# Sheet1.net
KiCad netlist of a schematic drawn in Altium Designer
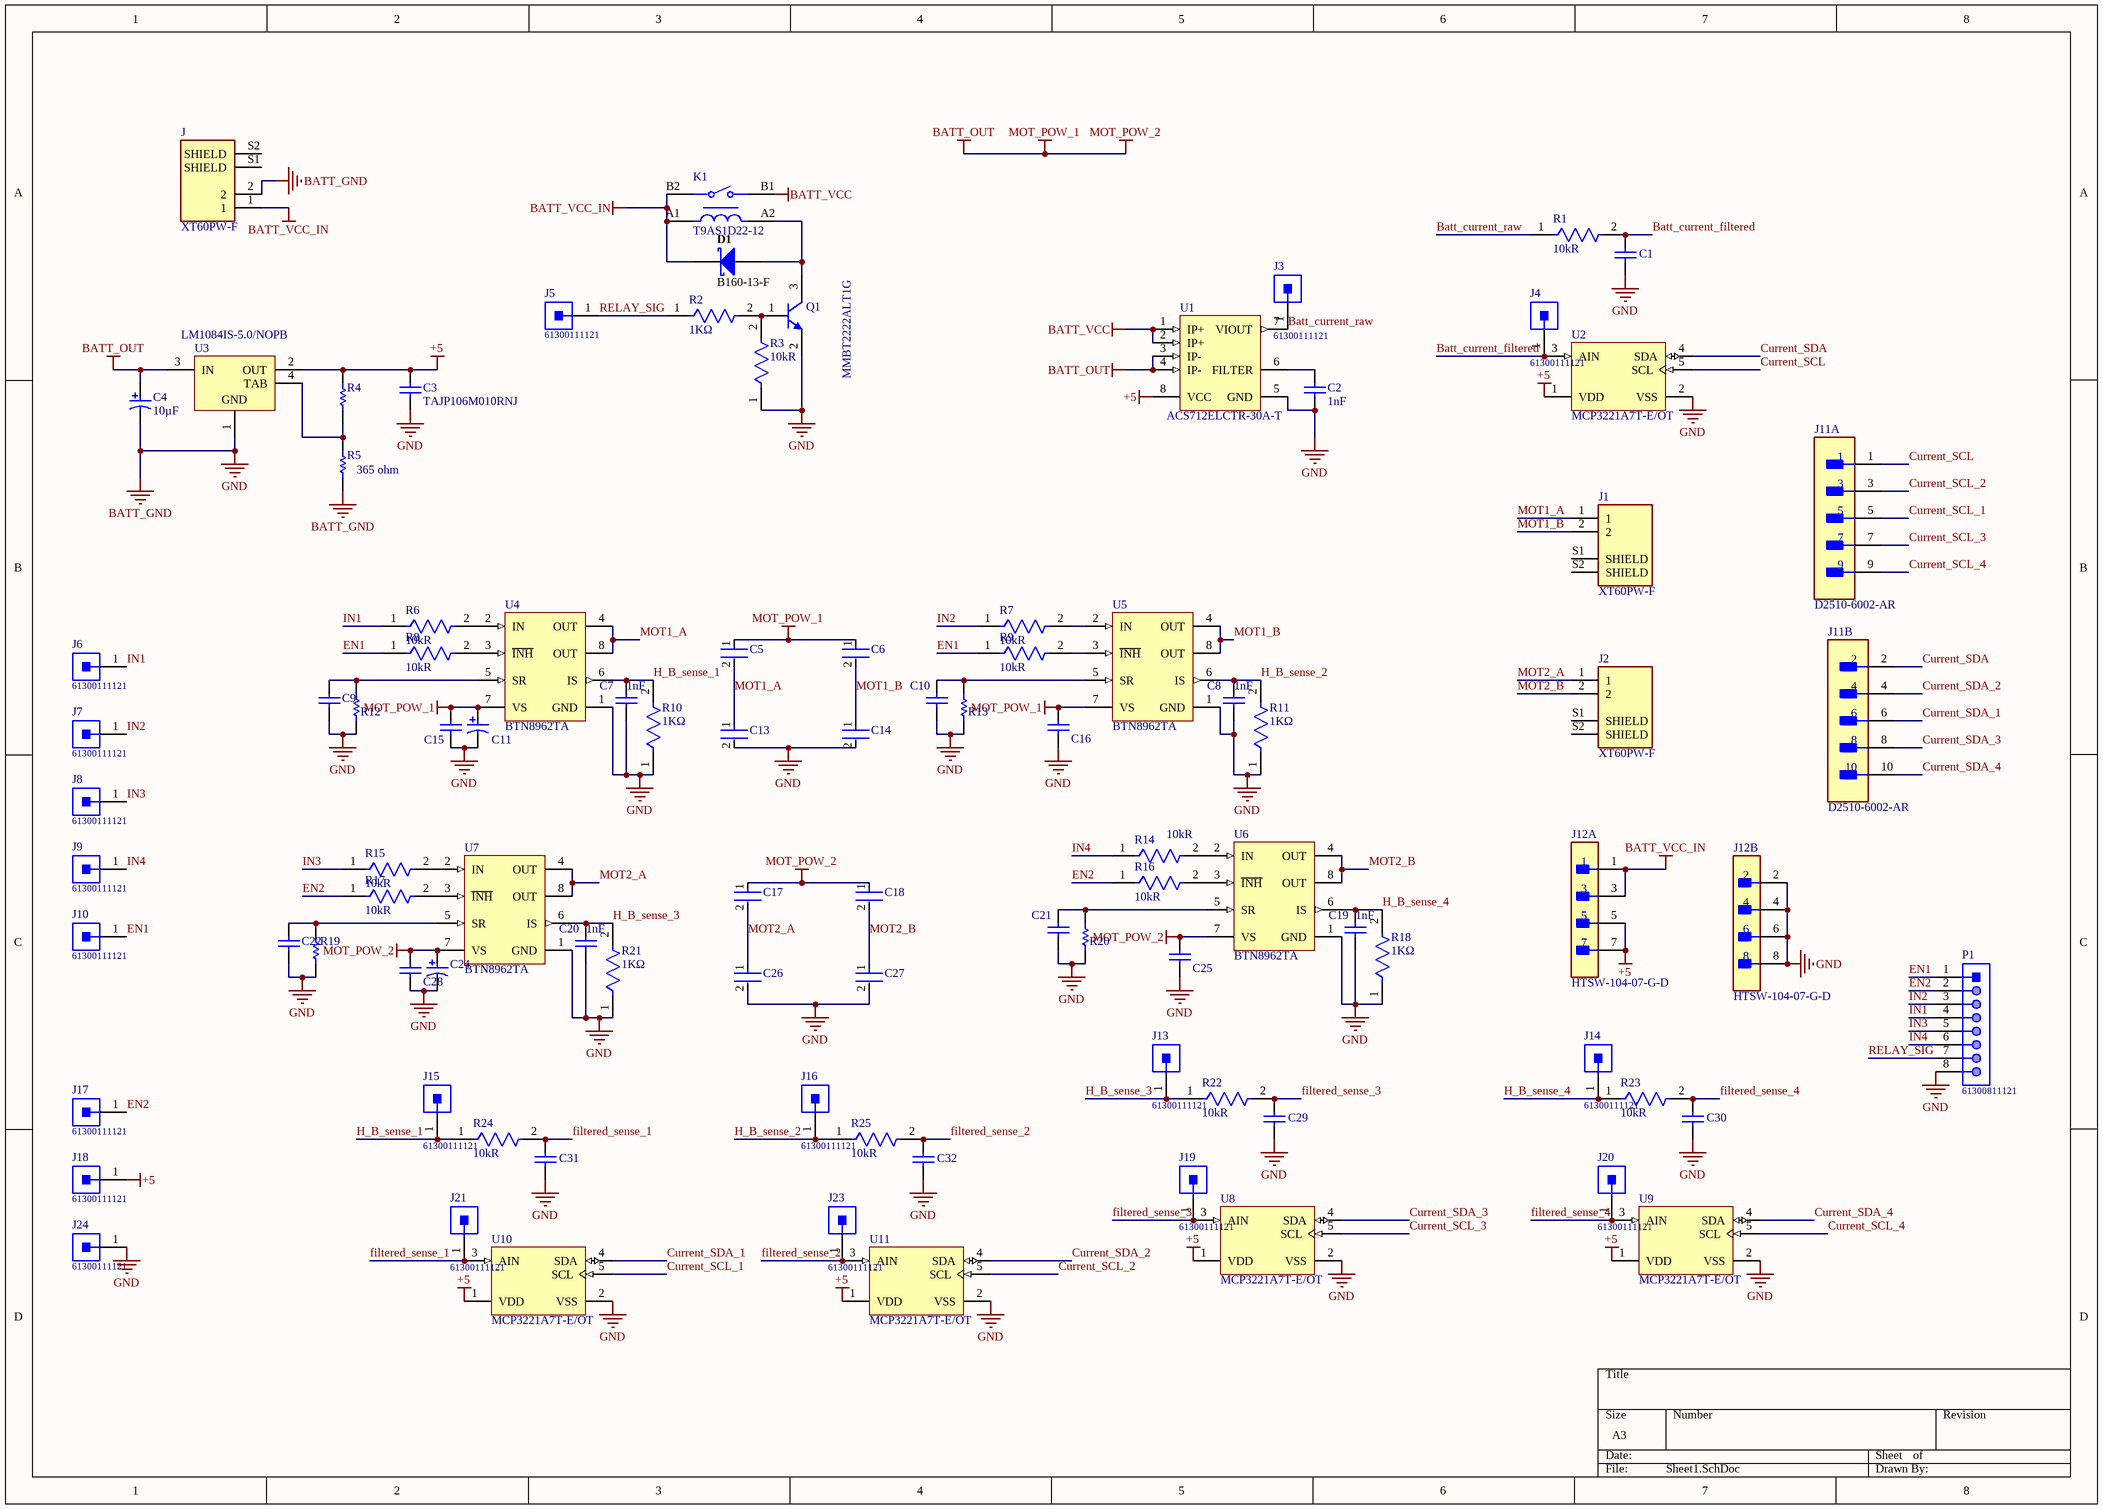
[diagram p0: Sheet1.SchDoc]

(export (version "E")
  (design (tool "Eeschema 10.0.6"))
  (components
    (comp (ref "C1")
      (value "GRM188R60J106ME47D")
      (footprint "CAPC1608X90X35NL10T15")
      (fields (field (name "MANUFACTURER") "Murata"))
      (libsource (lib "Altium Content Vault") (part "CAP"))
    )
    (comp (ref "C2")
      (value "1nF")
      (footprint "CAPC1608X95X40LL15T15")
      (fields (field (name "PART NUMBER") "VJ0603Y102KXACW1BC") (field (name "MANUFACTURER") "Vitramon"))
      (libsource (lib "Altium Content Vault") (part "CAP"))
    )
    (comp (ref "C3")
      (value "TAJP106M010RNJ")
      (footprint "CAPC2113X120X50ML20T30")
      (fields (field (name "MANUFACTURER") "AVX Interconnect / Elco"))
      (libsource (lib "Altium Content Vault") (part "CAP"))
    )
    (comp (ref "C4")
      (value "EEE-FK1V100UR")
      (footprint "PNSC-FK-V-B_V")
      (fields (field (name "MANUFACTURER") "Panasonic") (field (name "CAPACITANCE") "10µF"))
      (libsource (lib "Altium Content Vault") (part "CAP-P-2"))
    )
    (comp (ref "C5")
      (value "CC0805KRX7R7BB224")
      (footprint "FP-CC0805-0_85-MFG")
      (description "CAP CER 0.22UF 16V X7R 0805")
      (fields (field (name "TOLERANCE") "0.1") (field (name "MANUFACTURER") "Yageo"))
      (libsource (lib "Altium Content Vault") (part "11868f565c42a9108669ba33697ecf6"))
    )
    (comp (ref "C6")
      (value "CC0805KRX7R7BB224")
      (footprint "FP-CC0805-0_85-MFG")
      (description "CAP CER 0.22UF 16V X7R 0805")
      (fields (field (name "TOLERANCE") "0.1") (field (name "MANUFACTURER") "Yageo"))
      (libsource (lib "Altium Content Vault") (part "11868f565c42a9108669ba33697ecf6"))
    )
    (comp (ref "C7")
      (value "1nF")
      (footprint "CAPC1608X95X40LL15T15")
      (fields (field (name "PART NUMBER") "VJ0603Y102KXACW1BC") (field (name "MANUFACTURER") "Vitramon"))
      (libsource (lib "Altium Content Vault") (part "CAP"))
    )
    (comp (ref "C8")
      (value "1nF")
      (footprint "CAPC1608X95X40LL15T15")
      (fields (field (name "PART NUMBER") "VJ0603Y102KXACW1BC") (field (name "MANUFACTURER") "Vitramon"))
      (libsource (lib "Altium Content Vault") (part "CAP"))
    )
    (comp (ref "C9")
      (value "0603YC104KAZ2A")
      (footprint "CAPC1608X90X35ML15T15")
      (fields (field (name "MANUFACTURER") "AVX Interconnect / Elco"))
      (libsource (lib "Altium Content Vault") (part "CAP"))
    )
    (comp (ref "C10")
      (value "0603YC104KAZ2A")
      (footprint "CAPC1608X90X35ML15T15")
      (fields (field (name "MANUFACTURER") "AVX Interconnect / Elco"))
      (libsource (lib "Altium Content Vault") (part "CAP"))
    )
    (comp (ref "C11")
      (value "EEEFP1E471AP")
      (footprint "PNSC-FP-V-G_V")
      (fields (field (name "MANUFACTURER") "Panasonic"))
      (libsource (lib "Altium Content Vault") (part "CAP-P-2"))
    )
    (comp (ref "C13")
      (value "CC0805KRX7R7BB224")
      (footprint "FP-CC0805-0_85-MFG")
      (description "CAP CER 0.22UF 16V X7R 0805")
      (fields (field (name "TOLERANCE") "0.1") (field (name "MANUFACTURER") "Yageo"))
      (libsource (lib "Altium Content Vault") (part "11868f565c42a9108669ba33697ecf6"))
    )
    (comp (ref "C14")
      (value "CC0805KRX7R7BB224")
      (footprint "FP-CC0805-0_85-MFG")
      (description "CAP CER 0.22UF 16V X7R 0805")
      (fields (field (name "TOLERANCE") "0.1") (field (name "MANUFACTURER") "Yageo"))
      (libsource (lib "Altium Content Vault") (part "11868f565c42a9108669ba33697ecf6"))
    )
    (comp (ref "C15")
      (value "0603YC104KAZ2A")
      (footprint "CAPC1608X90X35ML15T15")
      (fields (field (name "MANUFACTURER") "AVX Interconnect / Elco"))
      (libsource (lib "Altium Content Vault") (part "CAP"))
    )
    (comp (ref "C16")
      (value "0603YC104KAZ2A")
      (footprint "CAPC1608X90X35ML15T15")
      (fields (field (name "MANUFACTURER") "AVX Interconnect / Elco"))
      (libsource (lib "Altium Content Vault") (part "CAP"))
    )
    (comp (ref "C17")
      (value "CC0805KRX7R7BB224")
      (footprint "FP-CC0805-0_85-MFG")
      (description "CAP CER 0.22UF 16V X7R 0805")
      (fields (field (name "TOLERANCE") "0.1") (field (name "MANUFACTURER") "Yageo"))
      (libsource (lib "Altium Content Vault") (part "11868f565c42a9108669ba33697ecf6"))
    )
    (comp (ref "C18")
      (value "CC0805KRX7R7BB224")
      (footprint "FP-CC0805-0_85-MFG")
      (description "CAP CER 0.22UF 16V X7R 0805")
      (fields (field (name "TOLERANCE") "0.1") (field (name "MANUFACTURER") "Yageo"))
      (libsource (lib "Altium Content Vault") (part "11868f565c42a9108669ba33697ecf6"))
    )
    (comp (ref "C19")
      (value "1nF")
      (footprint "CAPC1608X95X40LL15T15")
      (fields (field (name "PART NUMBER") "VJ0603Y102KXACW1BC") (field (name "MANUFACTURER") "Vitramon"))
      (libsource (lib "Altium Content Vault") (part "CAP"))
    )
    (comp (ref "C20")
      (value "1nF")
      (footprint "CAPC1608X95X40LL15T15")
      (fields (field (name "PART NUMBER") "VJ0603Y102KXACW1BC") (field (name "MANUFACTURER") "Vitramon"))
      (libsource (lib "Altium Content Vault") (part "CAP"))
    )
    (comp (ref "C21")
      (value "0603YC104KAZ2A")
      (footprint "CAPC1608X90X35ML15T15")
      (fields (field (name "MANUFACTURER") "AVX Interconnect / Elco"))
      (libsource (lib "Altium Content Vault") (part "CAP"))
    )
    (comp (ref "C22")
      (value "0603YC104KAZ2A")
      (footprint "CAPC1608X90X35ML15T15")
      (fields (field (name "MANUFACTURER") "AVX Interconnect / Elco"))
      (libsource (lib "Altium Content Vault") (part "CAP"))
    )
    (comp (ref "C24")
      (value "EEEFP1E471AP")
      (footprint "PNSC-FP-V-G_V")
      (fields (field (name "MANUFACTURER") "Panasonic"))
      (libsource (lib "Altium Content Vault") (part "CAP-P-2"))
    )
    (comp (ref "C25")
      (value "0603YC104KAZ2A")
      (footprint "CAPC1608X90X35ML15T15")
      (fields (field (name "MANUFACTURER") "AVX Interconnect / Elco"))
      (libsource (lib "Altium Content Vault") (part "CAP"))
    )
    (comp (ref "C26")
      (value "CC0805KRX7R7BB224")
      (footprint "FP-CC0805-0_85-MFG")
      (description "CAP CER 0.22UF 16V X7R 0805")
      (fields (field (name "TOLERANCE") "0.1") (field (name "MANUFACTURER") "Yageo"))
      (libsource (lib "Altium Content Vault") (part "11868f565c42a9108669ba33697ecf6"))
    )
    (comp (ref "C27")
      (value "CC0805KRX7R7BB224")
      (footprint "FP-CC0805-0_85-MFG")
      (description "CAP CER 0.22UF 16V X7R 0805")
      (fields (field (name "TOLERANCE") "0.1") (field (name "MANUFACTURER") "Yageo"))
      (libsource (lib "Altium Content Vault") (part "11868f565c42a9108669ba33697ecf6"))
    )
    (comp (ref "C28")
      (value "0603YC104KAZ2A")
      (footprint "CAPC1608X90X35ML15T15")
      (fields (field (name "MANUFACTURER") "AVX Interconnect / Elco"))
      (libsource (lib "Altium Content Vault") (part "CAP"))
    )
    (comp (ref "C29")
      (value "GRM188R60J106ME47D")
      (footprint "CAPC1608X90X35NL10T15")
      (fields (field (name "MANUFACTURER") "Murata"))
      (libsource (lib "Altium Content Vault") (part "CAP"))
    )
    (comp (ref "C30")
      (value "GRM188R60J106ME47D")
      (footprint "CAPC1608X90X35NL10T15")
      (fields (field (name "MANUFACTURER") "Murata"))
      (libsource (lib "Altium Content Vault") (part "CAP"))
    )
    (comp (ref "C31")
      (value "GRM188R60J106ME47D")
      (footprint "CAPC1608X90X35NL10T15")
      (fields (field (name "MANUFACTURER") "Murata"))
      (libsource (lib "Altium Content Vault") (part "CAP"))
    )
    (comp (ref "C32")
      (value "GRM188R60J106ME47D")
      (footprint "CAPC1608X90X35NL10T15")
      (fields (field (name "MANUFACTURER") "Murata"))
      (libsource (lib "Altium Content Vault") (part "CAP"))
    )
    (comp (ref "D1")
      (value "B160-13-F")
      (footprint "DIOD-B1X0-2_V")
      (description "Surface Mount Schottky Barrier Rectifier, 1 A, -65 to 150 degC, 2-Pin SMA, RoHS, Tape and Reel")
      (fields (field (name "MANUFACTURER") "DiodesIncorporated"))
      (libsource (lib "Altium Content Vault") (part "DSKY_K1A2-2"))
    )
    (comp (ref "J")
      (value "XT60PW-F")
      (footprint "AMASS_XT60PW-F")
      (description "Socket DC Supply Connector Female")
      (fields
        (field (name "MF") "AMASS")
        (field (name "BUYPART") "https://www.snapeda.com/parts/XT60PW-F/AMASS/view-part/2890674/?ref=eda")
      )
      (libsource (lib "XT60PW-F") (part "XT60PW-F"))
    )
    (comp (ref "J1")
      (value "XT60PW-F")
      (footprint "AMASS_XT60PW-F")
      (description "Socket DC Supply Connector Female")
      (fields
        (field (name "MF") "AMASS")
        (field (name "BUYPART") "https://www.snapeda.com/parts/XT60PW-F/AMASS/view-part/2890674/?ref=eda")
      )
      (libsource (lib "") (part "XT60PW-F_1"))
    )
    (comp (ref "J2")
      (value "XT60PW-F")
      (footprint "AMASS_XT60PW-F")
      (description "Socket DC Supply Connector Female")
      (fields
        (field (name "MF") "AMASS")
        (field (name "BUYPART") "https://www.snapeda.com/parts/XT60PW-F/AMASS/view-part/2890674/?ref=eda")
      )
      (libsource (lib "") (part "XT60PW-F_1"))
    )
    (comp (ref "J3")
      (value "61300111121")
      (footprint "61300111121")
      (description "THT Vertical Pin Header WR-PHD, Pitch 2.54 mm, Single Row, 1 pins")
      (fields (field (name "MANUFACTURER") "Wurth Elektronik") (field (name "PUBLISHER") "WurthElektronik"))
      (libsource (lib "Altium Content Vault") (part "WE-CN-1P-M-R1"))
    )
    (comp (ref "J4")
      (value "61300111121")
      (footprint "61300111121")
      (description "THT Vertical Pin Header WR-PHD, Pitch 2.54 mm, Single Row, 1 pins")
      (fields (field (name "MANUFACTURER") "Wurth Elektronik") (field (name "PUBLISHER") "WurthElektronik"))
      (libsource (lib "Altium Content Vault") (part "WE-CN-1P-M-R1"))
    )
    (comp (ref "J5")
      (value "61300111121")
      (footprint "61300111121")
      (description "THT Vertical Pin Header WR-PHD, Pitch 2.54 mm, Single Row, 1 pins")
      (fields (field (name "MANUFACTURER") "Wurth Elektronik") (field (name "PUBLISHER") "WurthElektronik"))
      (libsource (lib "") (part "WE-CN-1P-M-R1_1"))
    )
    (comp (ref "J6")
      (value "61300111121")
      (footprint "61300111121")
      (description "THT Vertical Pin Header WR-PHD, Pitch 2.54 mm, Single Row, 1 pins")
      (fields (field (name "MANUFACTURER") "Wurth Elektronik") (field (name "PUBLISHER") "WurthElektronik"))
      (libsource (lib "") (part "WE-CN-1P-M-R1_1"))
    )
    (comp (ref "J7")
      (value "61300111121")
      (footprint "61300111121")
      (description "THT Vertical Pin Header WR-PHD, Pitch 2.54 mm, Single Row, 1 pins")
      (fields (field (name "MANUFACTURER") "Wurth Elektronik") (field (name "PUBLISHER") "WurthElektronik"))
      (libsource (lib "") (part "WE-CN-1P-M-R1_1"))
    )
    (comp (ref "J8")
      (value "61300111121")
      (footprint "61300111121")
      (description "THT Vertical Pin Header WR-PHD, Pitch 2.54 mm, Single Row, 1 pins")
      (fields (field (name "MANUFACTURER") "Wurth Elektronik") (field (name "PUBLISHER") "WurthElektronik"))
      (libsource (lib "") (part "WE-CN-1P-M-R1_1"))
    )
    (comp (ref "J9")
      (value "61300111121")
      (footprint "61300111121")
      (description "THT Vertical Pin Header WR-PHD, Pitch 2.54 mm, Single Row, 1 pins")
      (fields (field (name "MANUFACTURER") "Wurth Elektronik") (field (name "PUBLISHER") "WurthElektronik"))
      (libsource (lib "") (part "WE-CN-1P-M-R1_1"))
    )
    (comp (ref "J10")
      (value "61300111121")
      (footprint "61300111121")
      (description "THT Vertical Pin Header WR-PHD, Pitch 2.54 mm, Single Row, 1 pins")
      (fields (field (name "MANUFACTURER") "Wurth Elektronik") (field (name "PUBLISHER") "WurthElektronik"))
      (libsource (lib "") (part "WE-CN-1P-M-R1_1"))
    )
    (comp (ref "J11")
      (value "D2510-6002-AR")
      (footprint "FP-D2510-6002-AR-MFG")
      (description "CONN HEADER VERT 10POS 2.54MM")
      (fields
        (field (name "MANUFACTURER") "3M")
        (field (name "OCTOPART") "https://octopart.com/d2510-6002-ar-3m-8399032")
      )
      (libsource (lib "Altium Content Vault") (part "e3d72e3fae012c5d23a5abbd4905472"))
    )
    (comp (ref "J12")
      (value "HTSW-104-07-G-D")
      (footprint "FP-HTSW-104-07-G-D-MFG")
      (description "CONN HEADER VERT 8POS 2.54MM")
      (fields
        (field (name "MANUFACTURER") "Samtec")
        (field (name "OCTOPART") "https://octopart.com/htsw-104-07-g-d-samtec-10613822")
      )
      (libsource (lib "Altium Content Vault") (part "811e954b9c034aa737de4d9295cbe7e"))
    )
    (comp (ref "J13")
      (value "61300111121")
      (footprint "61300111121")
      (description "THT Vertical Pin Header WR-PHD, Pitch 2.54 mm, Single Row, 1 pins")
      (fields (field (name "MANUFACTURER") "Wurth Elektronik") (field (name "PUBLISHER") "WurthElektronik"))
      (libsource (lib "Altium Content Vault") (part "WE-CN-1P-M-R1"))
    )
    (comp (ref "J14")
      (value "61300111121")
      (footprint "61300111121")
      (description "THT Vertical Pin Header WR-PHD, Pitch 2.54 mm, Single Row, 1 pins")
      (fields (field (name "MANUFACTURER") "Wurth Elektronik") (field (name "PUBLISHER") "WurthElektronik"))
      (libsource (lib "Altium Content Vault") (part "WE-CN-1P-M-R1"))
    )
    (comp (ref "J15")
      (value "61300111121")
      (footprint "61300111121")
      (description "THT Vertical Pin Header WR-PHD, Pitch 2.54 mm, Single Row, 1 pins")
      (fields (field (name "MANUFACTURER") "Wurth Elektronik") (field (name "PUBLISHER") "WurthElektronik"))
      (libsource (lib "Altium Content Vault") (part "WE-CN-1P-M-R1"))
    )
    (comp (ref "J16")
      (value "61300111121")
      (footprint "61300111121")
      (description "THT Vertical Pin Header WR-PHD, Pitch 2.54 mm, Single Row, 1 pins")
      (fields (field (name "MANUFACTURER") "Wurth Elektronik") (field (name "PUBLISHER") "WurthElektronik"))
      (libsource (lib "Altium Content Vault") (part "WE-CN-1P-M-R1"))
    )
    (comp (ref "J17")
      (value "61300111121")
      (footprint "61300111121")
      (description "THT Vertical Pin Header WR-PHD, Pitch 2.54 mm, Single Row, 1 pins")
      (fields (field (name "MANUFACTURER") "Wurth Elektronik") (field (name "PUBLISHER") "WurthElektronik"))
      (libsource (lib "") (part "WE-CN-1P-M-R1_1"))
    )
    (comp (ref "J18")
      (value "61300111121")
      (footprint "61300111121")
      (description "THT Vertical Pin Header WR-PHD, Pitch 2.54 mm, Single Row, 1 pins")
      (fields (field (name "MANUFACTURER") "Wurth Elektronik") (field (name "PUBLISHER") "WurthElektronik"))
      (libsource (lib "") (part "WE-CN-1P-M-R1_1"))
    )
    (comp (ref "J19")
      (value "61300111121")
      (footprint "61300111121")
      (description "THT Vertical Pin Header WR-PHD, Pitch 2.54 mm, Single Row, 1 pins")
      (fields (field (name "MANUFACTURER") "Wurth Elektronik") (field (name "PUBLISHER") "WurthElektronik"))
      (libsource (lib "Altium Content Vault") (part "WE-CN-1P-M-R1"))
    )
    (comp (ref "J20")
      (value "61300111121")
      (footprint "61300111121")
      (description "THT Vertical Pin Header WR-PHD, Pitch 2.54 mm, Single Row, 1 pins")
      (fields (field (name "MANUFACTURER") "Wurth Elektronik") (field (name "PUBLISHER") "WurthElektronik"))
      (libsource (lib "Altium Content Vault") (part "WE-CN-1P-M-R1"))
    )
    (comp (ref "J21")
      (value "61300111121")
      (footprint "61300111121")
      (description "THT Vertical Pin Header WR-PHD, Pitch 2.54 mm, Single Row, 1 pins")
      (fields (field (name "MANUFACTURER") "Wurth Elektronik") (field (name "PUBLISHER") "WurthElektronik"))
      (libsource (lib "Altium Content Vault") (part "WE-CN-1P-M-R1"))
    )
    (comp (ref "J23")
      (value "61300111121")
      (footprint "61300111121")
      (description "THT Vertical Pin Header WR-PHD, Pitch 2.54 mm, Single Row, 1 pins")
      (fields (field (name "MANUFACTURER") "Wurth Elektronik") (field (name "PUBLISHER") "WurthElektronik"))
      (libsource (lib "Altium Content Vault") (part "WE-CN-1P-M-R1"))
    )
    (comp (ref "J24")
      (value "61300111121")
      (footprint "61300111121")
      (description "THT Vertical Pin Header WR-PHD, Pitch 2.54 mm, Single Row, 1 pins")
      (fields (field (name "MANUFACTURER") "Wurth Elektronik") (field (name "PUBLISHER") "WurthElektronik"))
      (libsource (lib "") (part "WE-CN-1P-M-R1_1"))
    )
    (comp (ref "K1")
      (value "T9AS1D22-12")
      (footprint "FP-T9AS1D22-12-MFG")
      (description "RELAY GEN PURPOSE SPST 30A 12V")
      (fields
        (field (name "OCTOPART") "https://octopart.com/t9as1d22-12-te+connectivity-46521723")
        (field (name "MANUFACTURER") "TE Connectivity")
      )
      (libsource (lib "Altium Content Vault") (part "8e293d1f856185b239982dffafedd3a"))
    )
    (comp (ref "P1")
      (value "61300811121")
      (footprint "61300811121")
      (description "THT Vertical Pin Header WR-PHD, Pitch 2.54 mm, Single Row, 8 pins")
      (fields (field (name "MANUFACTURER") "Wurth Elektronik") (field (name "PUBLISHER") "WurthElektronik"))
      (libsource (lib "Altium Content Vault") (part "WE-CN-1P-M-R8"))
    )
    (comp (ref "Q1")
      (value "MMBT2222ALT1G")
      (footprint "ONSC-SOT-23-3-318-08_V")
      (description "General Purpose Transistor, NPN Silicon, 3-Pin SOT-23, Pb-Free, Tape and Reel")
      (fields (field (name "MANUFACTURER") "On Semiconductor"))
      (libsource (lib "Altium Content Vault") (part "ONSC-NPN-B1E2C3-3"))
    )
    (comp (ref "R1")
      (value "MCT0603MD1002BP100")
      (footprint "FP-MCT0603-IPC_B")
      (description "RES SMD 100 OHM 1% 1/8W 0603")
      (fields (field (name "RESISTANCE") "10kR") (field (name "TOLERANCE") "0.1%"))
      (libsource (lib "Altium Content Vault") (part "1029c3af85768c4190bb7ad29bc67b5"))
    )
    (comp (ref "R2")
      (value "1KΩ")
      (footprint "FP-RP73P-1J-MFG")
      (description "RES SMD 1K OHM 0.1% 1/6W 0603")
      (fields (field (name "TOLERANCE") "0.001") (field (name "MANUFACTURER PART NUMBER") "RP73PF1J1K0BTDF"))
      (libsource (lib "Altium Content Vault") (part "1029c3af85768c4190bb7ad29bc67b5"))
    )
    (comp (ref "R3")
      (value "MCT0603MD1002BP100")
      (footprint "FP-MCT0603-IPC_B")
      (description "RES SMD 100 OHM 1% 1/8W 0603")
      (fields (field (name "RESISTANCE") "10kR") (field (name "TOLERANCE") "0.1%"))
      (libsource (lib "Altium Content Vault") (part "1029c3af85768c4190bb7ad29bc67b5"))
    )
    (comp (ref "R4")
      (value "ERJ-3EKF1210V")
      (footprint "RESC1608X55X30ML15T15")
      (fields (field (name "MANUFACTURER") "Panasonic"))
      (libsource (lib "Altium Content Vault") (part "RES"))
    )
    (comp (ref "R5")
      (value "365 ohm")
      (footprint "RESC1608X55X30LL15T15")
      (fields (field (name "PART NUMBER") "ERJ-3EKF3650V") (field (name "MANUFACTURER") "Panasonic"))
      (libsource (lib "Altium Content Vault") (part "RES"))
    )
    (comp (ref "R6")
      (value "MCT0603MD1002BP100")
      (footprint "FP-MCT0603-IPC_B")
      (description "RES SMD 100 OHM 1% 1/8W 0603")
      (fields (field (name "RESISTANCE") "10kR") (field (name "TOLERANCE") "0.1%"))
      (libsource (lib "Altium Content Vault") (part "1029c3af85768c4190bb7ad29bc67b5"))
    )
    (comp (ref "R7")
      (value "MCT0603MD1002BP100")
      (footprint "FP-MCT0603-IPC_B")
      (description "RES SMD 100 OHM 1% 1/8W 0603")
      (fields (field (name "RESISTANCE") "10kR") (field (name "TOLERANCE") "0.1%"))
      (libsource (lib "Altium Content Vault") (part "1029c3af85768c4190bb7ad29bc67b5"))
    )
    (comp (ref "R8")
      (value "MCT0603MD1002BP100")
      (footprint "FP-MCT0603-IPC_B")
      (description "RES SMD 100 OHM 1% 1/8W 0603")
      (fields (field (name "RESISTANCE") "10kR") (field (name "TOLERANCE") "0.1%"))
      (libsource (lib "Altium Content Vault") (part "1029c3af85768c4190bb7ad29bc67b5"))
    )
    (comp (ref "R9")
      (value "MCT0603MD1002BP100")
      (footprint "FP-MCT0603-IPC_B")
      (description "RES SMD 100 OHM 1% 1/8W 0603")
      (fields (field (name "RESISTANCE") "10kR") (field (name "TOLERANCE") "0.1%"))
      (libsource (lib "Altium Content Vault") (part "1029c3af85768c4190bb7ad29bc67b5"))
    )
    (comp (ref "R10")
      (value "1KΩ")
      (footprint "FP-RP73P-1J-MFG")
      (description "RES SMD 1K OHM 0.1% 1/6W 0603")
      (fields (field (name "TOLERANCE") "0.001") (field (name "MANUFACTURER PART NUMBER") "RP73PF1J1K0BTDF"))
      (libsource (lib "Altium Content Vault") (part "1029c3af85768c4190bb7ad29bc67b5"))
    )
    (comp (ref "R11")
      (value "1KΩ")
      (footprint "FP-RP73P-1J-MFG")
      (description "RES SMD 1K OHM 0.1% 1/6W 0603")
      (fields (field (name "TOLERANCE") "0.001") (field (name "MANUFACTURER PART NUMBER") "RP73PF1J1K0BTDF"))
      (libsource (lib "Altium Content Vault") (part "1029c3af85768c4190bb7ad29bc67b5"))
    )
    (comp (ref "R12")
      (value "CRCW0603510RFKEA")
      (footprint "RESC1609X50X30NL10T20")
      (fields (field (name "MANUFACTURER") "Vishay Dale"))
      (libsource (lib "Altium Content Vault") (part "RES"))
    )
    (comp (ref "R13")
      (value "CRCW0603510RFKEA")
      (footprint "RESC1609X50X30NL10T20")
      (fields (field (name "MANUFACTURER") "Vishay Dale"))
      (libsource (lib "Altium Content Vault") (part "RES"))
    )
    (comp (ref "R14")
      (value "MCT0603MD1002BP100")
      (footprint "FP-MCT0603-IPC_B")
      (description "RES SMD 100 OHM 1% 1/8W 0603")
      (fields (field (name "RESISTANCE") "10kR") (field (name "TOLERANCE") "0.1%"))
      (libsource (lib "Altium Content Vault") (part "1029c3af85768c4190bb7ad29bc67b5"))
    )
    (comp (ref "R15")
      (value "MCT0603MD1002BP100")
      (footprint "FP-MCT0603-IPC_B")
      (description "RES SMD 100 OHM 1% 1/8W 0603")
      (fields (field (name "RESISTANCE") "10kR") (field (name "TOLERANCE") "0.1%"))
      (libsource (lib "Altium Content Vault") (part "1029c3af85768c4190bb7ad29bc67b5"))
    )
    (comp (ref "R16")
      (value "MCT0603MD1002BP100")
      (footprint "FP-MCT0603-IPC_B")
      (description "RES SMD 100 OHM 1% 1/8W 0603")
      (fields (field (name "RESISTANCE") "10kR") (field (name "TOLERANCE") "0.1%"))
      (libsource (lib "Altium Content Vault") (part "1029c3af85768c4190bb7ad29bc67b5"))
    )
    (comp (ref "R17")
      (value "MCT0603MD1002BP100")
      (footprint "FP-MCT0603-IPC_B")
      (description "RES SMD 100 OHM 1% 1/8W 0603")
      (fields (field (name "RESISTANCE") "10kR") (field (name "TOLERANCE") "0.1%"))
      (libsource (lib "Altium Content Vault") (part "1029c3af85768c4190bb7ad29bc67b5"))
    )
    (comp (ref "R18")
      (value "1KΩ")
      (footprint "FP-RP73P-1J-MFG")
      (description "RES SMD 1K OHM 0.1% 1/6W 0603")
      (fields (field (name "TOLERANCE") "0.001") (field (name "MANUFACTURER PART NUMBER") "RP73PF1J1K0BTDF"))
      (libsource (lib "Altium Content Vault") (part "1029c3af85768c4190bb7ad29bc67b5"))
    )
    (comp (ref "R19")
      (value "CRCW0603510RFKEA")
      (footprint "RESC1609X50X30NL10T20")
      (fields (field (name "MANUFACTURER") "Vishay Dale"))
      (libsource (lib "Altium Content Vault") (part "RES"))
    )
    (comp (ref "R20")
      (value "CRCW0603510RFKEA")
      (footprint "RESC1609X50X30NL10T20")
      (fields (field (name "MANUFACTURER") "Vishay Dale"))
      (libsource (lib "Altium Content Vault") (part "RES"))
    )
    (comp (ref "R21")
      (value "1KΩ")
      (footprint "FP-RP73P-1J-MFG")
      (description "RES SMD 1K OHM 0.1% 1/6W 0603")
      (fields (field (name "TOLERANCE") "0.001") (field (name "MANUFACTURER PART NUMBER") "RP73PF1J1K0BTDF"))
      (libsource (lib "Altium Content Vault") (part "1029c3af85768c4190bb7ad29bc67b5"))
    )
    (comp (ref "R22")
      (value "MCT0603MD1002BP100")
      (footprint "FP-MCT0603-IPC_B")
      (description "RES SMD 100 OHM 1% 1/8W 0603")
      (fields (field (name "RESISTANCE") "10kR") (field (name "TOLERANCE") "0.1%"))
      (libsource (lib "Altium Content Vault") (part "1029c3af85768c4190bb7ad29bc67b5"))
    )
    (comp (ref "R23")
      (value "MCT0603MD1002BP100")
      (footprint "FP-MCT0603-IPC_B")
      (description "RES SMD 100 OHM 1% 1/8W 0603")
      (fields (field (name "RESISTANCE") "10kR") (field (name "TOLERANCE") "0.1%"))
      (libsource (lib "Altium Content Vault") (part "1029c3af85768c4190bb7ad29bc67b5"))
    )
    (comp (ref "R24")
      (value "MCT0603MD1002BP100")
      (footprint "FP-MCT0603-IPC_B")
      (description "RES SMD 100 OHM 1% 1/8W 0603")
      (fields (field (name "RESISTANCE") "10kR") (field (name "TOLERANCE") "0.1%"))
      (libsource (lib "Altium Content Vault") (part "1029c3af85768c4190bb7ad29bc67b5"))
    )
    (comp (ref "R25")
      (value "MCT0603MD1002BP100")
      (footprint "FP-MCT0603-IPC_B")
      (description "RES SMD 100 OHM 1% 1/8W 0603")
      (fields (field (name "RESISTANCE") "10kR") (field (name "TOLERANCE") "0.1%"))
      (libsource (lib "Altium Content Vault") (part "1029c3af85768c4190bb7ad29bc67b5"))
    )
    (comp (ref "U1")
      (value "ACS712ELCTR-30A-T")
      (footprint "ALEG-LC-8_V")
      (fields (field (name "MANUFACTURER") "Allegro Microsystems"))
      (libsource (lib "Altium Content Vault") (part "ALEG-ACS712-SOIC-8"))
    )
    (comp (ref "U2")
      (value "MCP3221A7T-E/OT")
      (footprint "SOT-23-OT5_N")
      (libsource (lib "Altium Content Vault") (part "CON-ADC-MCP3021-5"))
    )
    (comp (ref "U3")
      (value "LM1084IS-5.0/NOPB")
      (footprint "KTT0003B_L")
      (description "5A Low Dropout Positive Regulators, 3-pin TO-263, Pb-Free")
      (fields (field (name "MANUFACTURER") "Texas Instruments"))
      (libsource (lib "Altium Content Vault") (part "PM-REG-LM1086-SOT4"))
    )
    (comp (ref "U4")
      (value "BTN8962TA")
      (footprint "INF-PG-TO263-7-1_N")
      (description "High Current PN Half Bridge, 5.5 to 40 V, 7 uA Iq, PG-TO263-7, Reel, Green")
      (fields (field (name "MANUFACTURER") "Infineon"))
      (libsource (lib "Altium Content Vault") (part "INF-BTN89X2TA-PG-TO263-7-1-7"))
    )
    (comp (ref "U5")
      (value "BTN8962TA")
      (footprint "INF-PG-TO263-7-1_N")
      (description "High Current PN Half Bridge, 5.5 to 40 V, 7 uA Iq, PG-TO263-7, Reel, Green")
      (fields (field (name "MANUFACTURER") "Infineon"))
      (libsource (lib "Altium Content Vault") (part "INF-BTN89X2TA-PG-TO263-7-1-7"))
    )
    (comp (ref "U6")
      (value "BTN8962TA")
      (footprint "INF-PG-TO263-7-1_N")
      (description "High Current PN Half Bridge, 5.5 to 40 V, 7 uA Iq, PG-TO263-7, Reel, Green")
      (fields (field (name "MANUFACTURER") "Infineon"))
      (libsource (lib "Altium Content Vault") (part "INF-BTN89X2TA-PG-TO263-7-1-7"))
    )
    (comp (ref "U7")
      (value "BTN8962TA")
      (footprint "INF-PG-TO263-7-1_N")
      (description "High Current PN Half Bridge, 5.5 to 40 V, 7 uA Iq, PG-TO263-7, Reel, Green")
      (fields (field (name "MANUFACTURER") "Infineon"))
      (libsource (lib "Altium Content Vault") (part "INF-BTN89X2TA-PG-TO263-7-1-7"))
    )
    (comp (ref "U8")
      (value "MCP3221A7T-E/OT")
      (footprint "SOT-23-OT5_N")
      (libsource (lib "Altium Content Vault") (part "CON-ADC-MCP3021-5"))
    )
    (comp (ref "U9")
      (value "MCP3221A7T-E/OT")
      (footprint "SOT-23-OT5_N")
      (libsource (lib "Altium Content Vault") (part "CON-ADC-MCP3021-5"))
    )
    (comp (ref "U10")
      (value "MCP3221A7T-E/OT")
      (footprint "SOT-23-OT5_N")
      (libsource (lib "Altium Content Vault") (part "CON-ADC-MCP3021-5"))
    )
    (comp (ref "U11")
      (value "MCP3221A7T-E/OT")
      (footprint "SOT-23-OT5_N")
      (libsource (lib "Altium Content Vault") (part "CON-ADC-MCP3021-5"))
    )
  )
  (nets
    (net (code "1") (name "+5") (class "Default")
      (node (ref "C3") (pin "2") (pinfunction "2_2") (pintype "passive"))
      (node (ref "J12") (pin "5") (pinfunction "5_5") (pintype "passive"))
      (node (ref "J12") (pin "7") (pinfunction "7_7") (pintype "passive"))
      (node (ref "J18") (pin "1") (pinfunction "1_1") (pintype "passive"))
      (node (ref "R4") (pin "2") (pinfunction "2_2") (pintype "passive"))
      (node (ref "U1") (pin "8") (pinfunction "VCC_8") (pintype "power_in"))
      (node (ref "U10") (pin "1") (pinfunction "VDD_1") (pintype "power_in"))
      (node (ref "U11") (pin "1") (pinfunction "VDD_1") (pintype "power_in"))
      (node (ref "U2") (pin "1") (pinfunction "VDD_1") (pintype "power_in"))
      (node (ref "U3") (pin "2") (pinfunction "OUT_2") (pintype "power_in"))
      (node (ref "U8") (pin "1") (pinfunction "VDD_1") (pintype "power_in"))
      (node (ref "U9") (pin "1") (pinfunction "VDD_1") (pintype "power_in"))
    )
    (net (code "2") (name "/Batt_current_filtered") (class "Default")
      (node (ref "C1") (pin "2") (pinfunction "2_2") (pintype "passive"))
      (node (ref "J4") (pin "1") (pinfunction "1_1") (pintype "passive"))
      (node (ref "R1") (pin "2") (pinfunction "2_2") (pintype "passive"))
      (node (ref "U2") (pin "3") (pinfunction "AIN_3") (pintype "input"))
    )
    (net (code "3") (name "/Batt_current_raw") (class "Default")
      (node (ref "J3") (pin "1") (pinfunction "1_1") (pintype "passive"))
      (node (ref "R1") (pin "1") (pinfunction "1_1") (pintype "passive"))
      (node (ref "U1") (pin "7") (pinfunction "VIOUT_7") (pintype "output"))
    )
    (net (code "4") (name "/Current_SCL") (class "Default")
      (node (ref "J11") (pin "1") (pinfunction "1_1") (pintype "passive"))
      (node (ref "U2") (pin "5") (pinfunction "SCL_5") (pintype "input"))
    )
    (net (code "5") (name "/Current_SCL_1") (class "Default")
      (node (ref "J11") (pin "5") (pinfunction "5_5") (pintype "passive"))
      (node (ref "U10") (pin "5") (pinfunction "SCL_5") (pintype "input"))
    )
    (net (code "6") (name "/Current_SCL_2") (class "Default")
      (node (ref "J11") (pin "3") (pinfunction "3_3") (pintype "passive"))
      (node (ref "U11") (pin "5") (pinfunction "SCL_5") (pintype "input"))
    )
    (net (code "7") (name "/Current_SCL_3") (class "Default")
      (node (ref "J11") (pin "7") (pinfunction "7_7") (pintype "passive"))
      (node (ref "U8") (pin "5") (pinfunction "SCL_5") (pintype "input"))
    )
    (net (code "8") (name "/Current_SCL_4") (class "Default")
      (node (ref "J11") (pin "9") (pinfunction "9_9") (pintype "passive"))
      (node (ref "U9") (pin "5") (pinfunction "SCL_5") (pintype "input"))
    )
    (net (code "9") (name "/Current_SDA") (class "Default")
      (node (ref "J11") (pin "2") (pinfunction "2_2") (pintype "passive"))
      (node (ref "U2") (pin "4") (pinfunction "SDA_4") (pintype "bidirectional"))
    )
    (net (code "10") (name "/Current_SDA_1") (class "Default")
      (node (ref "J11") (pin "6") (pinfunction "6_6") (pintype "passive"))
      (node (ref "U10") (pin "4") (pinfunction "SDA_4") (pintype "bidirectional"))
    )
    (net (code "11") (name "/Current_SDA_2") (class "Default")
      (node (ref "J11") (pin "4") (pinfunction "4_4") (pintype "passive"))
      (node (ref "U11") (pin "4") (pinfunction "SDA_4") (pintype "bidirectional"))
    )
    (net (code "12") (name "/Current_SDA_3") (class "Default")
      (node (ref "J11") (pin "8") (pinfunction "8_8") (pintype "passive"))
      (node (ref "U8") (pin "4") (pinfunction "SDA_4") (pintype "bidirectional"))
    )
    (net (code "13") (name "/Current_SDA_4") (class "Default")
      (node (ref "J11") (pin "10") (pinfunction "10_10") (pintype "passive"))
      (node (ref "U9") (pin "4") (pinfunction "SDA_4") (pintype "bidirectional"))
    )
    (net (code "14") (name "/EN1") (class "Default")
      (node (ref "J10") (pin "1") (pinfunction "1_1") (pintype "passive"))
      (node (ref "P1") (pin "1") (pinfunction "1_1") (pintype "passive"))
      (node (ref "R8") (pin "1") (pinfunction "1_1") (pintype "passive"))
      (node (ref "R9") (pin "1") (pinfunction "1_1") (pintype "passive"))
    )
    (net (code "15") (name "/EN2") (class "Default")
      (node (ref "J17") (pin "1") (pinfunction "1_1") (pintype "passive"))
      (node (ref "P1") (pin "2") (pinfunction "2_2") (pintype "passive"))
      (node (ref "R16") (pin "1") (pinfunction "1_1") (pintype "passive"))
      (node (ref "R17") (pin "1") (pinfunction "1_1") (pintype "passive"))
    )
    (net (code "16") (name "/H_B_sense_1") (class "Default")
      (node (ref "C7") (pin "2") (pinfunction "2_2") (pintype "passive"))
      (node (ref "J15") (pin "1") (pinfunction "1_1") (pintype "passive"))
      (node (ref "R10") (pin "2") (pinfunction "2_2") (pintype "passive"))
      (node (ref "R24") (pin "1") (pinfunction "1_1") (pintype "passive"))
      (node (ref "U4") (pin "6") (pinfunction "IS_6") (pintype "output"))
    )
    (net (code "17") (name "/H_B_sense_2") (class "Default")
      (node (ref "C8") (pin "2") (pinfunction "2_2") (pintype "passive"))
      (node (ref "J16") (pin "1") (pinfunction "1_1") (pintype "passive"))
      (node (ref "R11") (pin "2") (pinfunction "2_2") (pintype "passive"))
      (node (ref "R25") (pin "1") (pinfunction "1_1") (pintype "passive"))
      (node (ref "U5") (pin "6") (pinfunction "IS_6") (pintype "output"))
    )
    (net (code "18") (name "/H_B_sense_3") (class "Default")
      (node (ref "C20") (pin "2") (pinfunction "2_2") (pintype "passive"))
      (node (ref "J13") (pin "1") (pinfunction "1_1") (pintype "passive"))
      (node (ref "R21") (pin "2") (pinfunction "2_2") (pintype "passive"))
      (node (ref "R22") (pin "1") (pinfunction "1_1") (pintype "passive"))
      (node (ref "U7") (pin "6") (pinfunction "IS_6") (pintype "output"))
    )
    (net (code "19") (name "/H_B_sense_4") (class "Default")
      (node (ref "C19") (pin "2") (pinfunction "2_2") (pintype "passive"))
      (node (ref "J14") (pin "1") (pinfunction "1_1") (pintype "passive"))
      (node (ref "R18") (pin "2") (pinfunction "2_2") (pintype "passive"))
      (node (ref "R23") (pin "1") (pinfunction "1_1") (pintype "passive"))
      (node (ref "U6") (pin "6") (pinfunction "IS_6") (pintype "output"))
    )
    (net (code "20") (name "/IN1") (class "Default")
      (node (ref "J6") (pin "1") (pinfunction "1_1") (pintype "passive"))
      (node (ref "P1") (pin "4") (pinfunction "4_4") (pintype "passive"))
      (node (ref "R6") (pin "1") (pinfunction "1_1") (pintype "passive"))
    )
    (net (code "21") (name "/IN2") (class "Default")
      (node (ref "J7") (pin "1") (pinfunction "1_1") (pintype "passive"))
      (node (ref "P1") (pin "3") (pinfunction "3_3") (pintype "passive"))
      (node (ref "R7") (pin "1") (pinfunction "1_1") (pintype "passive"))
    )
    (net (code "22") (name "/IN3") (class "Default")
      (node (ref "J8") (pin "1") (pinfunction "1_1") (pintype "passive"))
      (node (ref "P1") (pin "5") (pinfunction "5_5") (pintype "passive"))
      (node (ref "R15") (pin "1") (pinfunction "1_1") (pintype "passive"))
    )
    (net (code "23") (name "/IN4") (class "Default")
      (node (ref "J9") (pin "1") (pinfunction "1_1") (pintype "passive"))
      (node (ref "P1") (pin "6") (pinfunction "6_6") (pintype "passive"))
      (node (ref "R14") (pin "1") (pinfunction "1_1") (pintype "passive"))
    )
    (net (code "24") (name "/MOT1_A") (class "Default")
      (node (ref "C13") (pin "1") (pinfunction "1_1") (pintype "passive"))
      (node (ref "C5") (pin "2") (pinfunction "2_2") (pintype "passive"))
      (node (ref "J1") (pin "1") (pinfunction "1_1") (pintype "passive"))
      (node (ref "U4") (pin "4") (pinfunction "OUT_4") (pintype "power_in"))
      (node (ref "U4") (pin "8") (pinfunction "OUT_8") (pintype "power_in"))
    )
    (net (code "25") (name "/MOT1_B") (class "Default")
      (node (ref "C14") (pin "1") (pinfunction "1_1") (pintype "passive"))
      (node (ref "C6") (pin "2") (pinfunction "2_2") (pintype "passive"))
      (node (ref "J1") (pin "2") (pinfunction "2_2") (pintype "passive"))
      (node (ref "U5") (pin "4") (pinfunction "OUT_4") (pintype "power_in"))
      (node (ref "U5") (pin "8") (pinfunction "OUT_8") (pintype "power_in"))
    )
    (net (code "26") (name "/MOT2_A") (class "Default")
      (node (ref "C17") (pin "2") (pinfunction "2_2") (pintype "passive"))
      (node (ref "C26") (pin "1") (pinfunction "1_1") (pintype "passive"))
      (node (ref "J2") (pin "1") (pinfunction "1_1") (pintype "passive"))
      (node (ref "U7") (pin "4") (pinfunction "OUT_4") (pintype "power_in"))
      (node (ref "U7") (pin "8") (pinfunction "OUT_8") (pintype "power_in"))
    )
    (net (code "27") (name "/MOT2_B") (class "Default")
      (node (ref "C18") (pin "2") (pinfunction "2_2") (pintype "passive"))
      (node (ref "C27") (pin "1") (pinfunction "1_1") (pintype "passive"))
      (node (ref "J2") (pin "2") (pinfunction "2_2") (pintype "passive"))
      (node (ref "U6") (pin "4") (pinfunction "OUT_4") (pintype "power_in"))
      (node (ref "U6") (pin "8") (pinfunction "OUT_8") (pintype "power_in"))
    )
    (net (code "28") (name "/RELAY_SIG") (class "Default")
      (node (ref "J5") (pin "1") (pinfunction "1_1") (pintype "passive"))
      (node (ref "P1") (pin "7") (pinfunction "7_7") (pintype "passive"))
      (node (ref "R2") (pin "1") (pinfunction "1_1") (pintype "passive"))
    )
    (net (code "29") (name "/filtered_sense_1") (class "Default")
      (node (ref "C31") (pin "2") (pinfunction "2_2") (pintype "passive"))
      (node (ref "J21") (pin "1") (pinfunction "1_1") (pintype "passive"))
      (node (ref "R24") (pin "2") (pinfunction "2_2") (pintype "passive"))
      (node (ref "U10") (pin "3") (pinfunction "AIN_3") (pintype "input"))
    )
    (net (code "30") (name "/filtered_sense_2") (class "Default")
      (node (ref "C32") (pin "2") (pinfunction "2_2") (pintype "passive"))
      (node (ref "J23") (pin "1") (pinfunction "1_1") (pintype "passive"))
      (node (ref "R25") (pin "2") (pinfunction "2_2") (pintype "passive"))
      (node (ref "U11") (pin "3") (pinfunction "AIN_3") (pintype "input"))
    )
    (net (code "31") (name "/filtered_sense_3") (class "Default")
      (node (ref "C29") (pin "2") (pinfunction "2_2") (pintype "passive"))
      (node (ref "J19") (pin "1") (pinfunction "1_1") (pintype "passive"))
      (node (ref "R22") (pin "2") (pinfunction "2_2") (pintype "passive"))
      (node (ref "U8") (pin "3") (pinfunction "AIN_3") (pintype "input"))
    )
    (net (code "32") (name "/filtered_sense_4") (class "Default")
      (node (ref "C30") (pin "2") (pinfunction "2_2") (pintype "passive"))
      (node (ref "J20") (pin "1") (pinfunction "1_1") (pintype "passive"))
      (node (ref "R23") (pin "2") (pinfunction "2_2") (pintype "passive"))
      (node (ref "U9") (pin "3") (pinfunction "AIN_3") (pintype "input"))
    )
    (net (code "33") (name "BATT_GND") (class "Default")
      (node (ref "C1") (pin "1") (pinfunction "1_1") (pintype "passive"))
      (node (ref "C10") (pin "1") (pinfunction "1_1") (pintype "passive"))
      (node (ref "C11") (pin "2") (pinfunction "2_2") (pintype "passive"))
      (node (ref "C13") (pin "2") (pinfunction "2_2") (pintype "passive"))
      (node (ref "C14") (pin "2") (pinfunction "2_2") (pintype "passive"))
      (node (ref "C15") (pin "2") (pinfunction "2_2") (pintype "passive"))
      (node (ref "C16") (pin "2") (pinfunction "2_2") (pintype "passive"))
      (node (ref "C19") (pin "1") (pinfunction "1_1") (pintype "passive"))
      (node (ref "C2") (pin "1") (pinfunction "1_1") (pintype "passive"))
      (node (ref "C20") (pin "1") (pinfunction "1_1") (pintype "passive"))
      (node (ref "C21") (pin "1") (pinfunction "1_1") (pintype "passive"))
      (node (ref "C22") (pin "1") (pinfunction "1_1") (pintype "passive"))
      (node (ref "C24") (pin "2") (pinfunction "2_2") (pintype "passive"))
      (node (ref "C25") (pin "2") (pinfunction "2_2") (pintype "passive"))
      (node (ref "C26") (pin "2") (pinfunction "2_2") (pintype "passive"))
      (node (ref "C27") (pin "2") (pinfunction "2_2") (pintype "passive"))
      (node (ref "C28") (pin "2") (pinfunction "2_2") (pintype "passive"))
      (node (ref "C29") (pin "1") (pinfunction "1_1") (pintype "passive"))
      (node (ref "C3") (pin "1") (pinfunction "1_1") (pintype "passive"))
      (node (ref "C30") (pin "1") (pinfunction "1_1") (pintype "passive"))
      (node (ref "C31") (pin "1") (pinfunction "1_1") (pintype "passive"))
      (node (ref "C32") (pin "1") (pinfunction "1_1") (pintype "passive"))
      (node (ref "C4") (pin "2") (pinfunction "2_2") (pintype "passive"))
      (node (ref "C7") (pin "1") (pinfunction "1_1") (pintype "passive"))
      (node (ref "C8") (pin "1") (pinfunction "1_1") (pintype "passive"))
      (node (ref "C9") (pin "1") (pinfunction "1_1") (pintype "passive"))
      (node (ref "J") (pin "2") (pinfunction "2_2") (pintype "passive"))
      (node (ref "J12") (pin "2") (pinfunction "2_2") (pintype "passive"))
      (node (ref "J12") (pin "4") (pinfunction "4_4") (pintype "passive"))
      (node (ref "J12") (pin "6") (pinfunction "6_6") (pintype "passive"))
      (node (ref "J12") (pin "8") (pinfunction "8_8") (pintype "passive"))
      (node (ref "J24") (pin "1") (pinfunction "1_1") (pintype "passive"))
      (node (ref "P1") (pin "8") (pinfunction "8_8") (pintype "passive"))
      (node (ref "Q1") (pin "2") (pinfunction "E_2") (pintype "passive"))
      (node (ref "R10") (pin "1") (pinfunction "1_1") (pintype "passive"))
      (node (ref "R11") (pin "1") (pinfunction "1_1") (pintype "passive"))
      (node (ref "R12") (pin "1") (pinfunction "1_1") (pintype "passive"))
      (node (ref "R13") (pin "1") (pinfunction "1_1") (pintype "passive"))
      (node (ref "R18") (pin "1") (pinfunction "1_1") (pintype "passive"))
      (node (ref "R19") (pin "1") (pinfunction "1_1") (pintype "passive"))
      (node (ref "R20") (pin "1") (pinfunction "1_1") (pintype "passive"))
      (node (ref "R21") (pin "1") (pinfunction "1_1") (pintype "passive"))
      (node (ref "R3") (pin "1") (pinfunction "1_1") (pintype "passive"))
      (node (ref "R5") (pin "1") (pinfunction "1_1") (pintype "passive"))
      (node (ref "U1") (pin "5") (pinfunction "GND_5") (pintype "power_in"))
      (node (ref "U10") (pin "2") (pinfunction "VSS_2") (pintype "power_in"))
      (node (ref "U11") (pin "2") (pinfunction "VSS_2") (pintype "power_in"))
      (node (ref "U2") (pin "2") (pinfunction "VSS_2") (pintype "power_in"))
      (node (ref "U3") (pin "1") (pinfunction "GND_1") (pintype "power_in"))
      (node (ref "U4") (pin "1") (pinfunction "GND_1") (pintype "power_in"))
      (node (ref "U5") (pin "1") (pinfunction "GND_1") (pintype "power_in"))
      (node (ref "U6") (pin "1") (pinfunction "GND_1") (pintype "power_in"))
      (node (ref "U7") (pin "1") (pinfunction "GND_1") (pintype "power_in"))
      (node (ref "U8") (pin "2") (pinfunction "VSS_2") (pintype "power_in"))
      (node (ref "U9") (pin "2") (pinfunction "VSS_2") (pintype "power_in"))
    )
    (net (code "34") (name "BATT_OUT") (class "Default")
      (node (ref "C11") (pin "1") (pinfunction "1_1") (pintype "passive"))
      (node (ref "C15") (pin "1") (pinfunction "1_1") (pintype "passive"))
      (node (ref "C16") (pin "1") (pinfunction "1_1") (pintype "passive"))
      (node (ref "C17") (pin "1") (pinfunction "1_1") (pintype "passive"))
      (node (ref "C18") (pin "1") (pinfunction "1_1") (pintype "passive"))
      (node (ref "C24") (pin "1") (pinfunction "1_1") (pintype "passive"))
      (node (ref "C25") (pin "1") (pinfunction "1_1") (pintype "passive"))
      (node (ref "C28") (pin "1") (pinfunction "1_1") (pintype "passive"))
      (node (ref "C4") (pin "1") (pinfunction "1_1") (pintype "passive"))
      (node (ref "C5") (pin "1") (pinfunction "1_1") (pintype "passive"))
      (node (ref "C6") (pin "1") (pinfunction "1_1") (pintype "passive"))
      (node (ref "U1") (pin "3") (pinfunction "IP-_3") (pintype "input"))
      (node (ref "U1") (pin "4") (pinfunction "IP-_4") (pintype "input"))
      (node (ref "U3") (pin "3") (pinfunction "IN_3") (pintype "power_in"))
      (node (ref "U4") (pin "7") (pinfunction "VS_7") (pintype "power_in"))
      (node (ref "U5") (pin "7") (pinfunction "VS_7") (pintype "power_in"))
      (node (ref "U6") (pin "7") (pinfunction "VS_7") (pintype "power_in"))
      (node (ref "U7") (pin "7") (pinfunction "VS_7") (pintype "power_in"))
    )
    (net (code "35") (name "BATT_VCC") (class "Default")
      (node (ref "K1") (pin "B1") (pinfunction "B1_B1") (pintype "passive"))
      (node (ref "U1") (pin "1") (pinfunction "IP+_1") (pintype "input"))
      (node (ref "U1") (pin "2") (pinfunction "IP+_2") (pintype "input"))
    )
    (net (code "36") (name "BATT_VCC_IN") (class "Default")
      (node (ref "D1") (pin "1") (pinfunction "K_1") (pintype "passive"))
      (node (ref "J") (pin "1") (pinfunction "1_1") (pintype "passive"))
      (node (ref "J12") (pin "1") (pinfunction "1_1") (pintype "passive"))
      (node (ref "J12") (pin "3") (pinfunction "3_3") (pintype "passive"))
      (node (ref "K1") (pin "A1") (pinfunction "A1_A1") (pintype "passive"))
      (node (ref "K1") (pin "B2") (pinfunction "B2_B2") (pintype "passive"))
    )
    (net (code "37") (name "Net-(D1-A)") (class "Default")
      (node (ref "D1") (pin "2") (pinfunction "A_2") (pintype "passive"))
      (node (ref "K1") (pin "A2") (pinfunction "A2_A2") (pintype "passive"))
      (node (ref "Q1") (pin "3") (pinfunction "C_3") (pintype "passive"))
    )
    (net (code "38") (name "Net-(Q1-B)") (class "Default")
      (node (ref "Q1") (pin "1") (pinfunction "B_1") (pintype "passive"))
      (node (ref "R2") (pin "2") (pinfunction "2_2") (pintype "passive"))
      (node (ref "R3") (pin "2") (pinfunction "2_2") (pintype "passive"))
    )
    (net (code "39") (name "Net-(U1-FILTER)") (class "Default")
      (node (ref "C2") (pin "2") (pinfunction "2_2") (pintype "passive"))
      (node (ref "U1") (pin "6") (pinfunction "FILTER_6") (pintype "passive"))
    )
    (net (code "40") (name "Net-(U3-TAB)") (class "Default")
      (node (ref "R4") (pin "1") (pinfunction "1_1") (pintype "passive"))
      (node (ref "R5") (pin "2") (pinfunction "2_2") (pintype "passive"))
      (node (ref "U3") (pin "4") (pinfunction "TAB_4") (pintype "power_in"))
    )
    (net (code "41") (name "Net-(U4-IN)") (class "Default")
      (node (ref "R6") (pin "2") (pinfunction "2_2") (pintype "passive"))
      (node (ref "U4") (pin "2") (pinfunction "IN_2") (pintype "input"))
    )
    (net (code "42") (name "Net-(U4-SR)") (class "Default")
      (node (ref "C9") (pin "2") (pinfunction "2_2") (pintype "passive"))
      (node (ref "R12") (pin "2") (pinfunction "2_2") (pintype "passive"))
      (node (ref "U4") (pin "5") (pinfunction "SR_5") (pintype "input"))
    )
    (net (code "43") (name "Net-(U4-~{INH})") (class "Default")
      (node (ref "R8") (pin "2") (pinfunction "2_2") (pintype "passive"))
      (node (ref "U4") (pin "3") (pinfunction "~{INH}_3") (pintype "input"))
    )
    (net (code "44") (name "Net-(U5-IN)") (class "Default")
      (node (ref "R7") (pin "2") (pinfunction "2_2") (pintype "passive"))
      (node (ref "U5") (pin "2") (pinfunction "IN_2") (pintype "input"))
    )
    (net (code "45") (name "Net-(U5-SR)") (class "Default")
      (node (ref "C10") (pin "2") (pinfunction "2_2") (pintype "passive"))
      (node (ref "R13") (pin "2") (pinfunction "2_2") (pintype "passive"))
      (node (ref "U5") (pin "5") (pinfunction "SR_5") (pintype "input"))
    )
    (net (code "46") (name "Net-(U5-~{INH})") (class "Default")
      (node (ref "R9") (pin "2") (pinfunction "2_2") (pintype "passive"))
      (node (ref "U5") (pin "3") (pinfunction "~{INH}_3") (pintype "input"))
    )
    (net (code "47") (name "Net-(U6-IN)") (class "Default")
      (node (ref "R14") (pin "2") (pinfunction "2_2") (pintype "passive"))
      (node (ref "U6") (pin "2") (pinfunction "IN_2") (pintype "input"))
    )
    (net (code "48") (name "Net-(U6-SR)") (class "Default")
      (node (ref "C21") (pin "2") (pinfunction "2_2") (pintype "passive"))
      (node (ref "R20") (pin "2") (pinfunction "2_2") (pintype "passive"))
      (node (ref "U6") (pin "5") (pinfunction "SR_5") (pintype "input"))
    )
    (net (code "49") (name "Net-(U6-~{INH})") (class "Default")
      (node (ref "R16") (pin "2") (pinfunction "2_2") (pintype "passive"))
      (node (ref "U6") (pin "3") (pinfunction "~{INH}_3") (pintype "input"))
    )
    (net (code "50") (name "Net-(U7-IN)") (class "Default")
      (node (ref "R15") (pin "2") (pinfunction "2_2") (pintype "passive"))
      (node (ref "U7") (pin "2") (pinfunction "IN_2") (pintype "input"))
    )
    (net (code "51") (name "Net-(U7-SR)") (class "Default")
      (node (ref "C22") (pin "2") (pinfunction "2_2") (pintype "passive"))
      (node (ref "R19") (pin "2") (pinfunction "2_2") (pintype "passive"))
      (node (ref "U7") (pin "5") (pinfunction "SR_5") (pintype "input"))
    )
    (net (code "52") (name "Net-(U7-~{INH})") (class "Default")
      (node (ref "R17") (pin "2") (pinfunction "2_2") (pintype "passive"))
      (node (ref "U7") (pin "3") (pinfunction "~{INH}_3") (pintype "input"))
    )
    (net (code "53") (name "unconnected-(J-SHIELD-PadS1)") (class "Default")
      (node (ref "J") (pin "S1") (pinfunction "SHIELD_S1") (pintype "passive"))
    )
    (net (code "54") (name "unconnected-(J-SHIELD-PadS2)") (class "Default")
      (node (ref "J") (pin "S2") (pinfunction "SHIELD_S2") (pintype "passive"))
    )
    (net (code "55") (name "unconnected-(J1-SHIELD-PadS1)") (class "Default")
      (node (ref "J1") (pin "S1") (pinfunction "SHIELD_S1") (pintype "passive"))
    )
    (net (code "56") (name "unconnected-(J1-SHIELD-PadS2)") (class "Default")
      (node (ref "J1") (pin "S2") (pinfunction "SHIELD_S2") (pintype "passive"))
    )
    (net (code "57") (name "unconnected-(J2-SHIELD-PadS1)") (class "Default")
      (node (ref "J2") (pin "S1") (pinfunction "SHIELD_S1") (pintype "passive"))
    )
    (net (code "58") (name "unconnected-(J2-SHIELD-PadS2)") (class "Default")
      (node (ref "J2") (pin "S2") (pinfunction "SHIELD_S2") (pintype "passive"))
    )
  )
)
